# Breadboard_ProMicro_v3.net
KiCad netlist of a schematic drawn in EAGLE
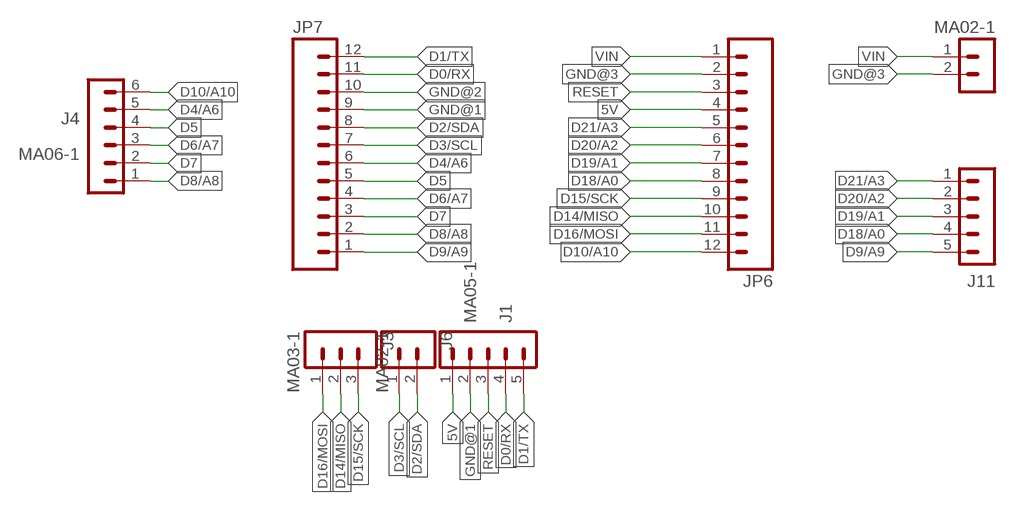
[diagram p0: schematic, sheet 1]

(export (version "E")
  (design (tool "Eeschema 10.0.6"))
  (components
    (comp (ref "J1")
      (value "MA05-1")
      (footprint "eagle-import:MA05-1")
      (libsource (lib "eagle-import") (part "MA05-1"))
    )
    (comp (ref "J3")
      (value "MA03-1")
      (footprint "eagle-import:MA03-1")
      (libsource (lib "eagle-import") (part "MA03-1"))
    )
    (comp (ref "J4")
      (value "MA06-1")
      (footprint "eagle-import:MA06-1")
      (libsource (lib "eagle-import") (part "MA06-1"))
    )
    (comp (ref "J6")
      (value "MA02-1")
      (footprint "eagle-import:MA02-1")
      (libsource (lib "eagle-import") (part "MA02-1"))
    )
    (comp (ref "J9")
      (value "MA02-1")
      (footprint "eagle-import:MA02-1")
      (libsource (lib "eagle-import") (part "MA02-1"))
    )
    (comp (ref "J11")
      (value "MA05-1")
      (footprint "eagle-import:MA05-1")
      (libsource (lib "eagle-import") (part "MA05-1"))
    )
    (comp (ref "JP6")
      (value "M12PTH")
      (footprint "eagle-import:1X12")
      (libsource (lib "eagle-import") (part "M12PTH"))
    )
    (comp (ref "JP7")
      (value "M12PTH")
      (footprint "eagle-import:1X12")
      (libsource (lib "eagle-import") (part "M12PTH"))
    )
  )
  (nets
    (net (code "1") (name "5V") (class "Default")
      (node (ref "J1") (pin "1") (pinfunction "1_1") (pintype "passive"))
      (node (ref "JP6") (pin "4") (pinfunction "4_4") (pintype "passive"))
    )
    (net (code "2") (name "D0{slash}RX") (class "Default")
      (node (ref "J1") (pin "4") (pinfunction "4_4") (pintype "passive"))
      (node (ref "JP7") (pin "11") (pinfunction "11_11") (pintype "passive"))
    )
    (net (code "3") (name "D1{slash}TX") (class "Default")
      (node (ref "J1") (pin "5") (pinfunction "5_5") (pintype "passive"))
      (node (ref "JP7") (pin "12") (pinfunction "12_12") (pintype "passive"))
    )
    (net (code "4") (name "D2{slash}SDA") (class "Default")
      (node (ref "J6") (pin "2") (pinfunction "2_2") (pintype "passive"))
      (node (ref "JP7") (pin "8") (pinfunction "8_8") (pintype "passive"))
    )
    (net (code "5") (name "D3{slash}SCL") (class "Default")
      (node (ref "J6") (pin "1") (pinfunction "1_1") (pintype "passive"))
      (node (ref "JP7") (pin "7") (pinfunction "7_7") (pintype "passive"))
    )
    (net (code "6") (name "D4{slash}A6") (class "Default")
      (node (ref "J4") (pin "5") (pinfunction "5_5") (pintype "passive"))
      (node (ref "JP7") (pin "6") (pinfunction "6_6") (pintype "passive"))
    )
    (net (code "7") (name "D5") (class "Default")
      (node (ref "J4") (pin "4") (pinfunction "4_4") (pintype "passive"))
      (node (ref "JP7") (pin "5") (pinfunction "5_5") (pintype "passive"))
    )
    (net (code "8") (name "D6{slash}A7") (class "Default")
      (node (ref "J4") (pin "3") (pinfunction "3_3") (pintype "passive"))
      (node (ref "JP7") (pin "4") (pinfunction "4_4") (pintype "passive"))
    )
    (net (code "9") (name "D7") (class "Default")
      (node (ref "J4") (pin "2") (pinfunction "2_2") (pintype "passive"))
      (node (ref "JP7") (pin "3") (pinfunction "3_3") (pintype "passive"))
    )
    (net (code "10") (name "D8{slash}A8") (class "Default")
      (node (ref "J4") (pin "1") (pinfunction "1_1") (pintype "passive"))
      (node (ref "JP7") (pin "2") (pinfunction "2_2") (pintype "passive"))
    )
    (net (code "11") (name "D9{slash}A9") (class "Default")
      (node (ref "J11") (pin "5") (pinfunction "5_5") (pintype "passive"))
      (node (ref "JP7") (pin "1") (pinfunction "1_1") (pintype "passive"))
    )
    (net (code "12") (name "D10{slash}A10") (class "Default")
      (node (ref "J4") (pin "6") (pinfunction "6_6") (pintype "passive"))
      (node (ref "JP6") (pin "12") (pinfunction "12_12") (pintype "passive"))
    )
    (net (code "13") (name "D14{slash}MISO") (class "Default")
      (node (ref "J3") (pin "2") (pinfunction "2_2") (pintype "passive"))
      (node (ref "JP6") (pin "10") (pinfunction "10_10") (pintype "passive"))
    )
    (net (code "14") (name "D15{slash}SCK") (class "Default")
      (node (ref "J3") (pin "3") (pinfunction "3_3") (pintype "passive"))
      (node (ref "JP6") (pin "9") (pinfunction "9_9") (pintype "passive"))
    )
    (net (code "15") (name "D16{slash}MOSI") (class "Default")
      (node (ref "J3") (pin "1") (pinfunction "1_1") (pintype "passive"))
      (node (ref "JP6") (pin "11") (pinfunction "11_11") (pintype "passive"))
    )
    (net (code "16") (name "D18{slash}A0") (class "Default")
      (node (ref "J11") (pin "4") (pinfunction "4_4") (pintype "passive"))
      (node (ref "JP6") (pin "8") (pinfunction "8_8") (pintype "passive"))
    )
    (net (code "17") (name "D19{slash}A1") (class "Default")
      (node (ref "J11") (pin "3") (pinfunction "3_3") (pintype "passive"))
      (node (ref "JP6") (pin "7") (pinfunction "7_7") (pintype "passive"))
    )
    (net (code "18") (name "D20{slash}A2") (class "Default")
      (node (ref "J11") (pin "2") (pinfunction "2_2") (pintype "passive"))
      (node (ref "JP6") (pin "6") (pinfunction "6_6") (pintype "passive"))
    )
    (net (code "19") (name "D21{slash}A3") (class "Default")
      (node (ref "J11") (pin "1") (pinfunction "1_1") (pintype "passive"))
      (node (ref "JP6") (pin "5") (pinfunction "5_5") (pintype "passive"))
    )
    (net (code "20") (name "GND@1") (class "Default")
      (node (ref "J1") (pin "2") (pinfunction "2_2") (pintype "passive"))
      (node (ref "JP7") (pin "9") (pinfunction "9_9") (pintype "passive"))
    )
    (net (code "21") (name "GND@2") (class "Default")
      (node (ref "JP7") (pin "10") (pinfunction "10_10") (pintype "passive"))
    )
    (net (code "22") (name "GND@3") (class "Default")
      (node (ref "J9") (pin "2") (pinfunction "2_2") (pintype "passive"))
      (node (ref "JP6") (pin "2") (pinfunction "2_2") (pintype "passive"))
    )
    (net (code "23") (name "RESET") (class "Default")
      (node (ref "J1") (pin "3") (pinfunction "3_3") (pintype "passive"))
      (node (ref "JP6") (pin "3") (pinfunction "3_3") (pintype "passive"))
    )
    (net (code "24") (name "VIN") (class "Default")
      (node (ref "J9") (pin "1") (pinfunction "1_1") (pintype "passive"))
      (node (ref "JP6") (pin "1") (pinfunction "1_1") (pintype "passive"))
    )
  )
)
